# Regulator.net
KiCad netlist of a schematic drawn in Altium Designer
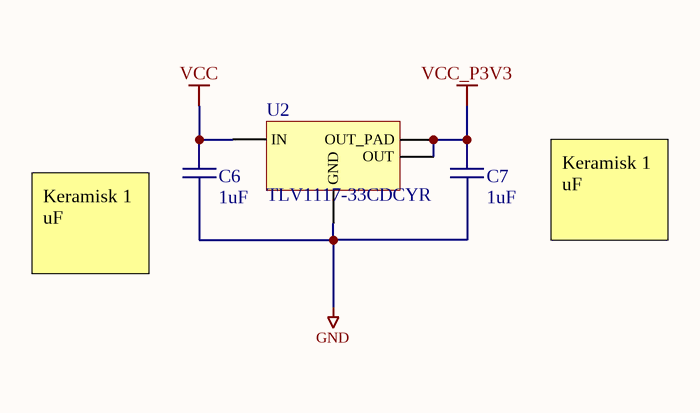
[diagram p0: Regulator.SchDoc]

(export (version "E")
  (design (tool "Eeschema 10.0.6"))
  (components
    (comp (ref "C6")
      (value "1uF")
      (footprint "CAPC0805(2012)100_N")
      (description "X7R 50V 10%")
      (libsource (lib "OVLib") (part "CAP"))
    )
    (comp (ref "C7")
      (value "1uF")
      (footprint "CAPC0805(2012)100_N")
      (description "X7R 50V 10%")
      (libsource (lib "OVLib") (part "CAP"))
    )
    (comp (ref "U2")
      (value "TLV1117-33CDCYR")
      (footprint "SOT230P700X180-4N")
      (description "3,3V Low dropout regulator")
      (libsource (lib "OVLib") (part "LDO_REGULATOR"))
    )
  )
  (nets
    (net (code "1") (name "GND") (class "Default")
      (node (ref "C6") (pin "1") (pinfunction "1_1") (pintype "passive"))
      (node (ref "C7") (pin "1") (pinfunction "1_1") (pintype "passive"))
      (node (ref "U2") (pin "1") (pinfunction "GND_1") (pintype "power_in"))
    )
    (net (code "2") (name "VCC") (class "Default")
      (node (ref "C6") (pin "2") (pinfunction "2_2") (pintype "passive"))
      (node (ref "U2") (pin "3") (pinfunction "IN_3") (pintype "power_in"))
    )
    (net (code "3") (name "VCC_P3V3") (class "Default")
      (node (ref "C7") (pin "2") (pinfunction "2_2") (pintype "passive"))
      (node (ref "U2") (pin "2") (pinfunction "OUT_PAD_2") (pintype "power_in"))
      (node (ref "U2") (pin "4") (pinfunction "OUT_4") (pintype "power_in"))
    )
  )
)
